# BSPD_v8.net
KiCad netlist of a schematic drawn in EAGLE
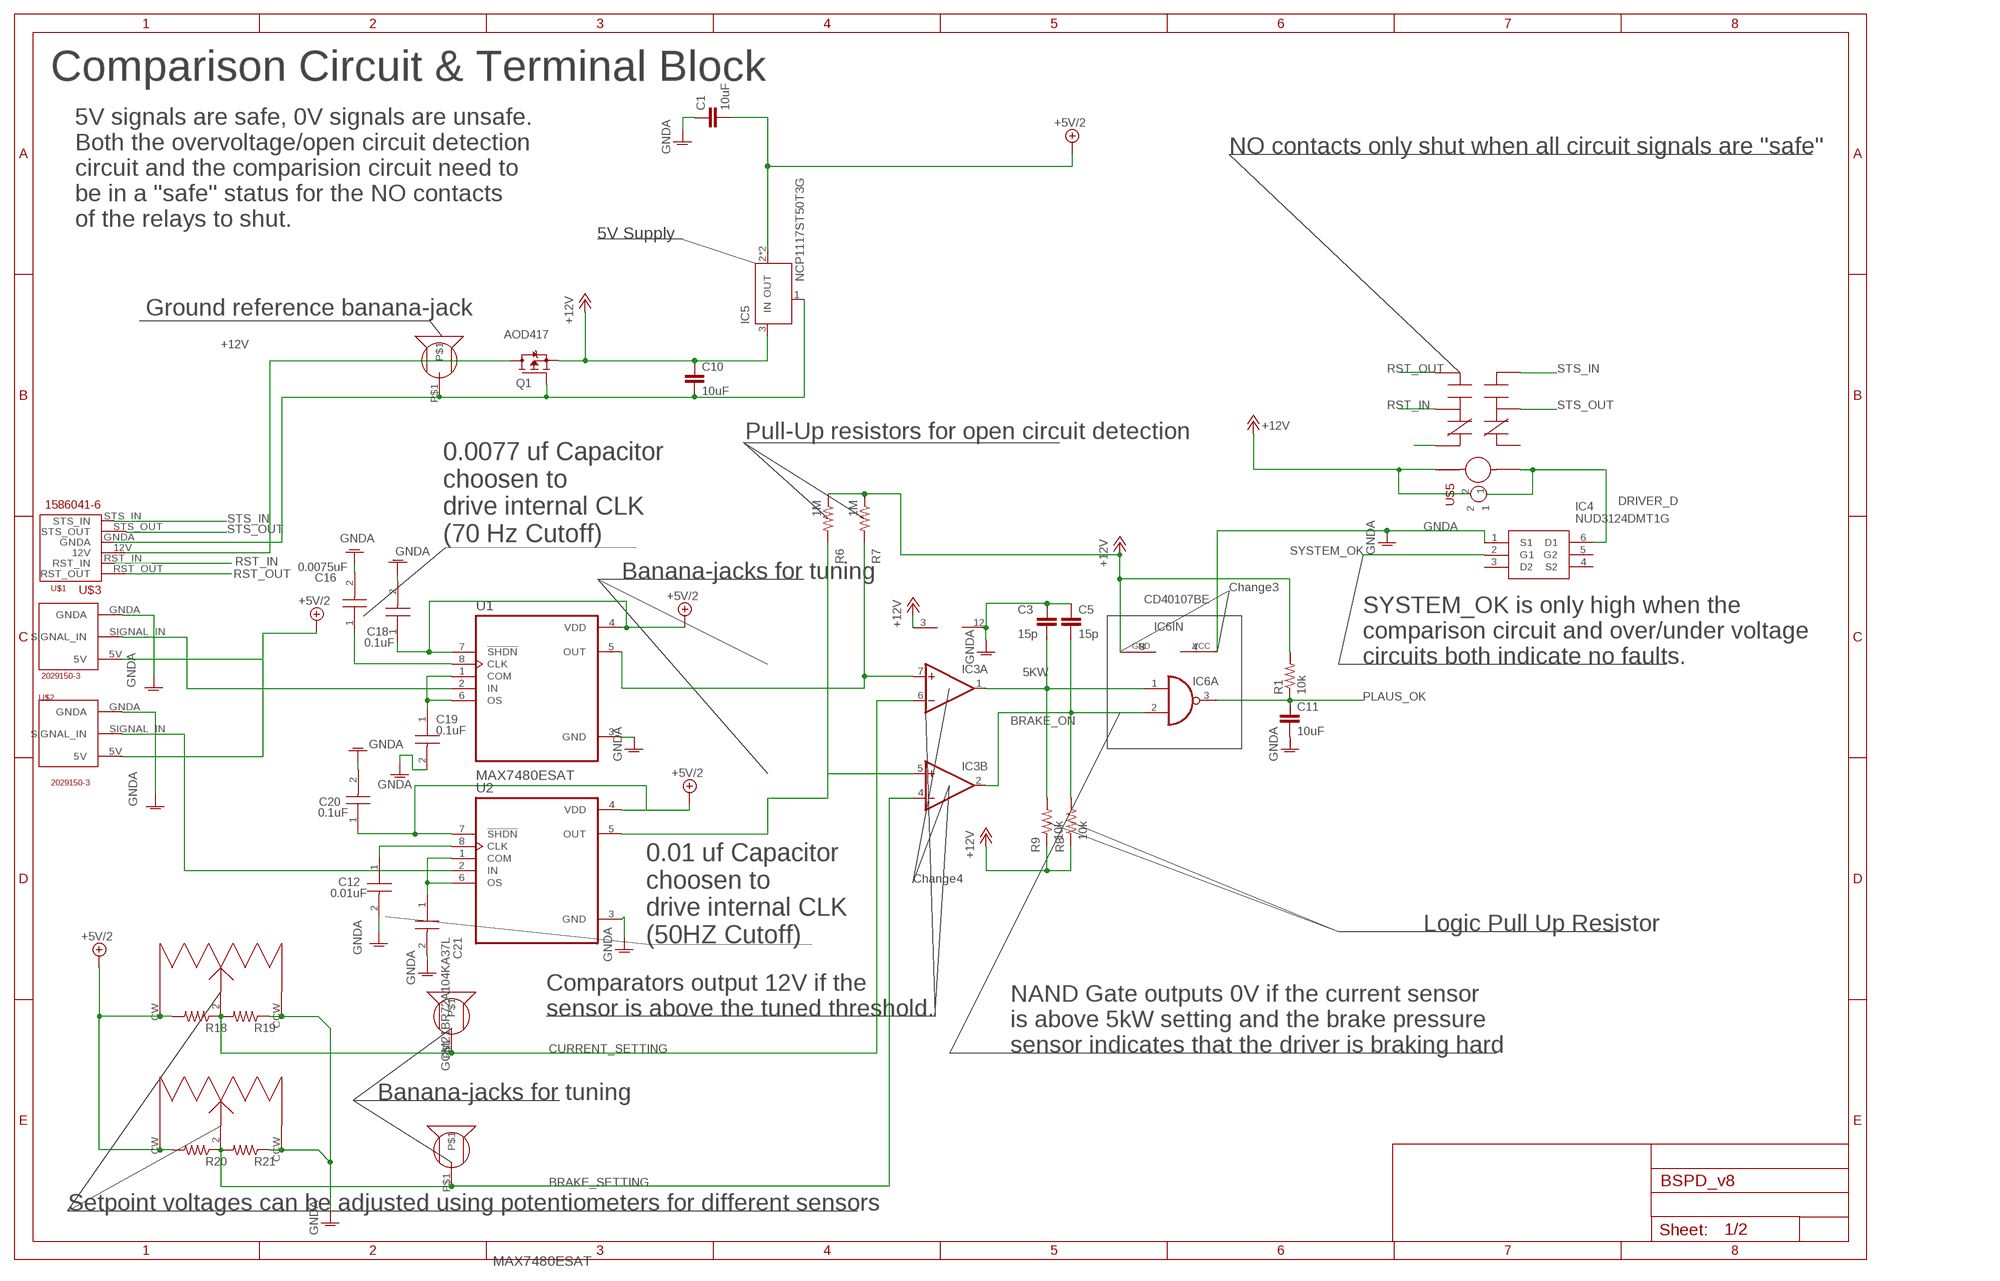
[diagram p0: schematic, sheet 1]
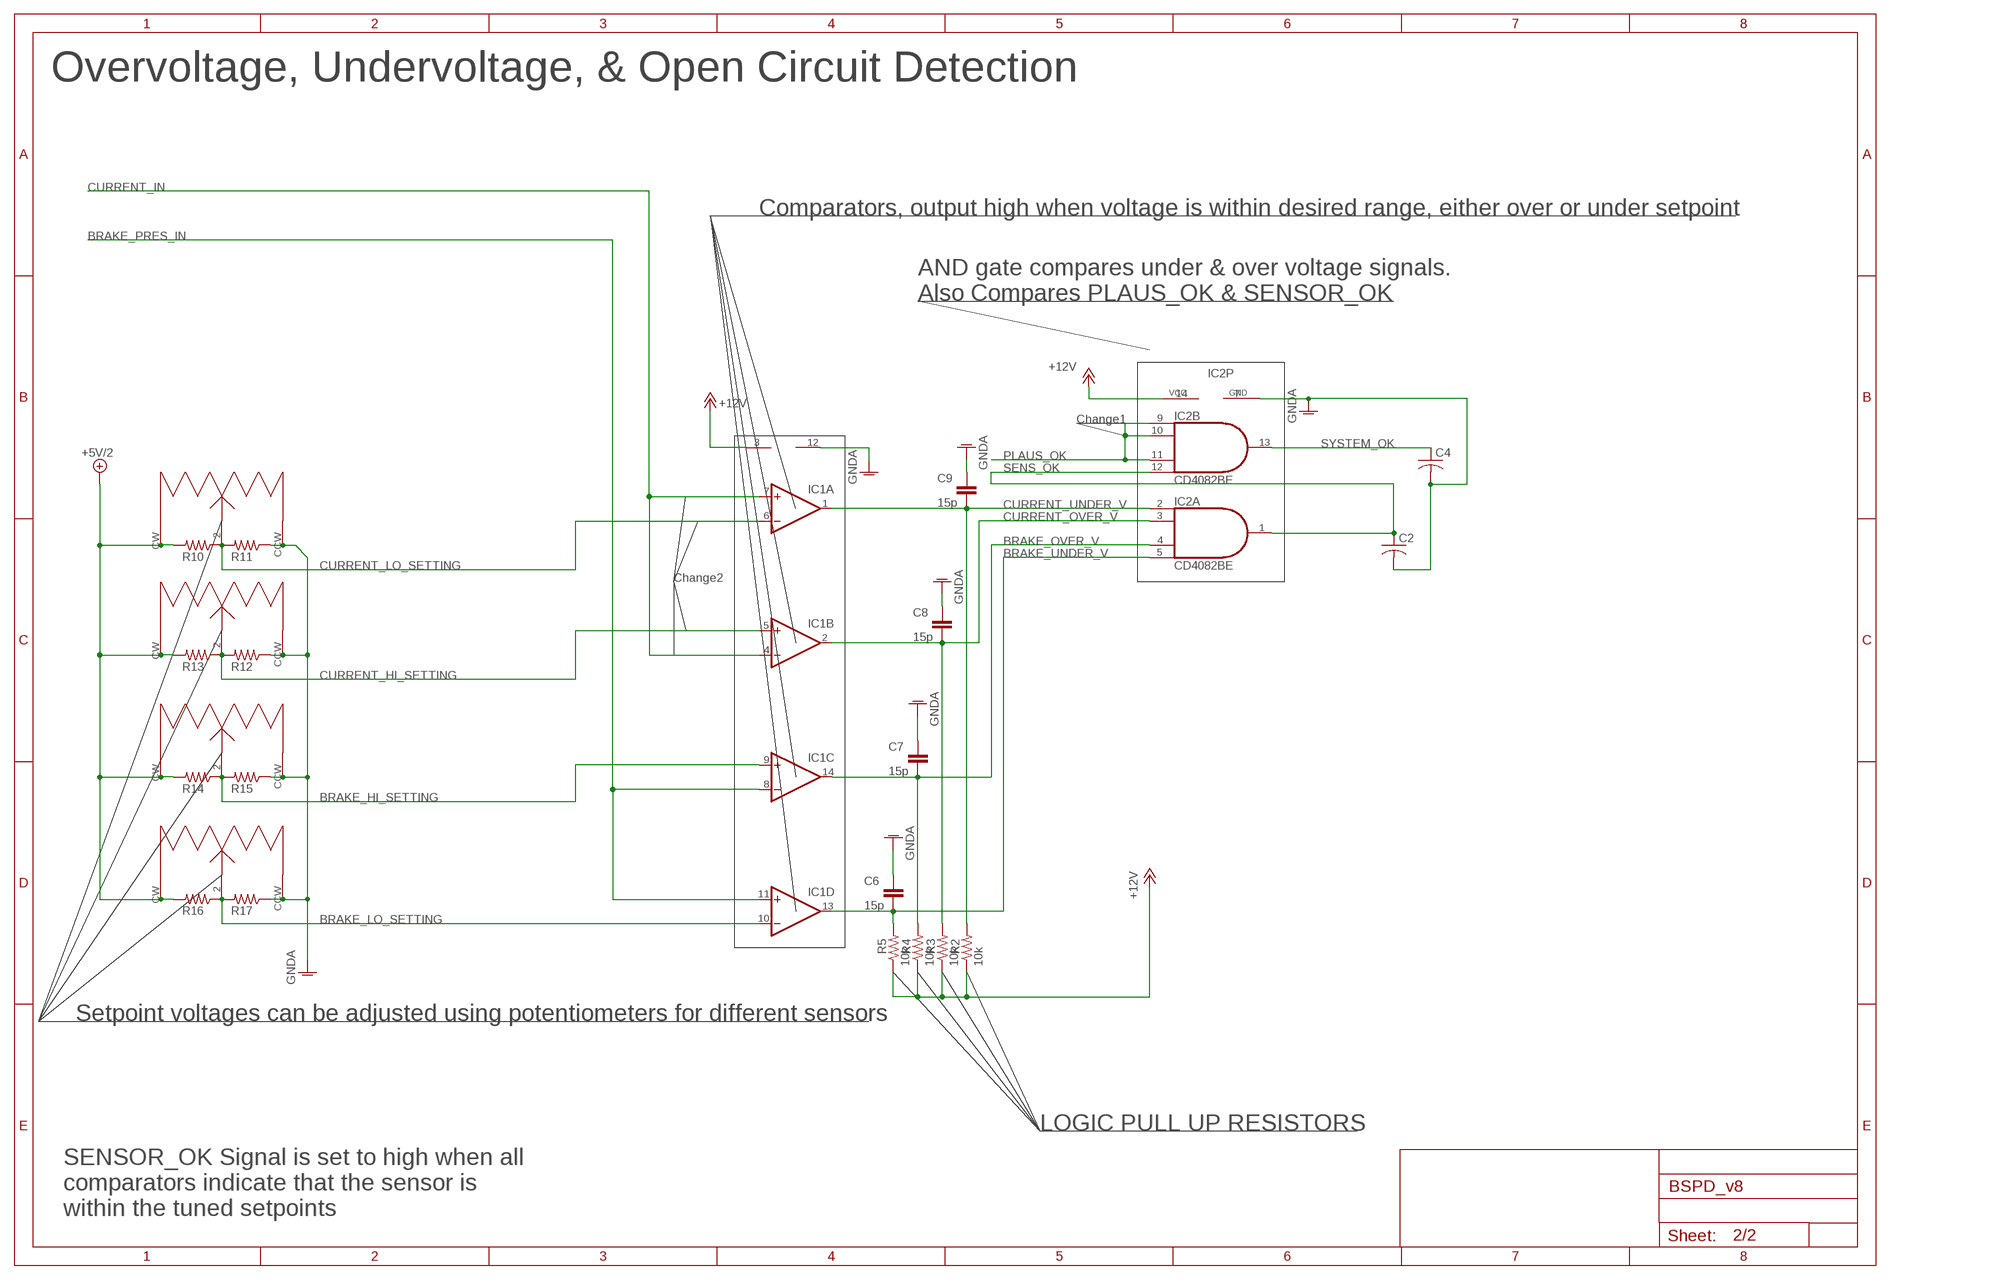
[diagram p1: schematic, sheet 2]

(export (version "E")
  (design (tool "Eeschema 10.0.6"))
  (components
    (comp (ref "C1")
      (value "10uF")
      (footprint "eagle-import:C0805")
      (libsource (lib "eagle-import") (part "resistor_348_C-EUC0805"))
    )
    (comp (ref "C3")
      (value "15p")
      (footprint "eagle-import:C0805")
      (libsource (lib "eagle-import") (part "C-EUC0805"))
    )
    (comp (ref "C5")
      (value "15p")
      (footprint "eagle-import:C0805")
      (libsource (lib "eagle-import") (part "C-EUC0805"))
    )
    (comp (ref "C10")
      (value "10uF")
      (footprint "eagle-import:C0805")
      (libsource (lib "eagle-import") (part "resistor_348_C-EUC0805"))
    )
    (comp (ref "C11")
      (value "10uF")
      (footprint "eagle-import:C0805")
      (libsource (lib "eagle-import") (part "resistor_348_C-EUC0805"))
    )
    (comp (ref "C12")
      (value "0.01uF")
      (footprint "eagle-import:CAPC2012X95N")
      (fields
        (field (name "MANUFACTURER_PART_NUMBER") "GRM2195C1H103JA01D")
        (field (name "MOUSER_PART_NUMBER") "81-GRM215C1H103JA01D")
      )
      (libsource (lib "eagle-import") (part "GRM2195C1H103JA01D"))
    )
    (comp (ref "C16")
      (value "0.0075uF")
      (footprint "eagle-import:CAPC2012X95N")
      (fields
        (field (name "MANUFACTURER_PART_NUMBER") "GRM2195C1H752JA01D")
        (field (name "MOUSER_PART_NUMBER") "81-GRM2195C1H752JA1D")
      )
      (libsource (lib "eagle-import") (part "GRM2195C1H752JA01D"))
    )
    (comp (ref "C18")
      (value "0.1uF")
      (footprint "eagle-import:CAPC2012X140N")
      (fields
        (field (name "MANUFACTURER_PART_NUMBER") "GCM21BR72A104KA37L")
        (field (name "MOUSER_PART_NUMBER") "81-GCM21BR72A104KA7L")
      )
      (libsource (lib "eagle-import") (part "GCM21BR72A104KA37L"))
    )
    (comp (ref "C19")
      (value "0.1uF")
      (footprint "eagle-import:CAPC2012X140N")
      (fields
        (field (name "MANUFACTURER_PART_NUMBER") "GCM21BR72A104KA37L")
        (field (name "MOUSER_PART_NUMBER") "81-GCM21BR72A104KA7L")
      )
      (libsource (lib "eagle-import") (part "GCM21BR72A104KA37L"))
    )
    (comp (ref "C20")
      (value "0.1uF")
      (footprint "eagle-import:CAPC2012X140N")
      (fields
        (field (name "MANUFACTURER_PART_NUMBER") "GCM21BR72A104KA37L")
        (field (name "MOUSER_PART_NUMBER") "81-GCM21BR72A104KA7L")
      )
      (libsource (lib "eagle-import") (part "GCM21BR72A104KA37L"))
    )
    (comp (ref "C21")
      (value "GCM21BR72A104KA37L")
      (footprint "eagle-import:CAPC2012X140N")
      (fields (field (name "MOUSER_PART_NUMBER") "81-GCM21BR72A104KA7L"))
      (libsource (lib "eagle-import") (part "GCM21BR72A104KA37L"))
    )
    (comp (ref "IC3")
      (value "4AMP_P11+7N")
      (footprint "eagle-import:DIL14")
      (libsource (lib "eagle-import") (part "4AMP_P11+7N"))
    )
    (comp (ref "IC4")
      (value "NUD3124DMT1G")
      (footprint "eagle-import:SOT95P275X110-6N")
      (fields (field (name "MOUSER_PART_NUMBER") "863-NUD3124DMT1G"))
      (libsource (lib "eagle-import") (part "NUD3124DMT1G"))
    )
    (comp (ref "IC5")
      (value "NCP1117ST50T3G")
      (footprint "eagle-import:SOT223")
      (libsource (lib "eagle-import") (part "NCP1117ST50T3G"))
    )
    (comp (ref "IC6")
      (value "CD40107BE")
      (footprint "eagle-import:DIL08")
      (libsource (lib "eagle-import") (part "CD40107BE"))
    )
    (comp (ref "Q1")
      (value "AOD417")
      (footprint "eagle-import:TO252")
      (fields (field (name "MF") "ON Semiconductor") (field (name "MP") "FDD4141"))
      (libsource (lib "eagle-import") (part "FDD4141TO252"))
    )
    (comp (ref "R1")
      (value "10k")
      (footprint "eagle-import:M0805")
      (libsource (lib "eagle-import") (part "R-US_M0805"))
    )
    (comp (ref "R6")
      (value "1M")
      (footprint "eagle-import:M0805")
      (libsource (lib "eagle-import") (part "resistor_R-US_M0805"))
    )
    (comp (ref "R7")
      (value "1M")
      (footprint "eagle-import:M0805")
      (libsource (lib "eagle-import") (part "resistor_R-US_M0805"))
    )
    (comp (ref "R8")
      (value "10k")
      (footprint "eagle-import:M0805")
      (libsource (lib "eagle-import") (part "resistor_R-US_M0805"))
    )
    (comp (ref "R9")
      (value "10k")
      (footprint "eagle-import:M0805")
      (libsource (lib "eagle-import") (part "resistor_R-US_M0805"))
    )
    (comp (ref "R18")
      (value "R-US_M0805")
      (footprint "eagle-import:M0805")
      (libsource (lib "eagle-import") (part "resistor_R-US_M0805"))
    )
    (comp (ref "R19")
      (value "R-US_M0805")
      (footprint "eagle-import:M0805")
      (libsource (lib "eagle-import") (part "resistor_R-US_M0805"))
    )
    (comp (ref "R20")
      (value "R-US_M0805")
      (footprint "eagle-import:M0805")
      (libsource (lib "eagle-import") (part "resistor_R-US_M0805"))
    )
    (comp (ref "R21")
      (value "R-US_M0805")
      (footprint "eagle-import:M0805")
      (libsource (lib "eagle-import") (part "resistor_R-US_M0805"))
    )
    (comp (ref "U$1")
      (value "2029150-3")
      (footprint "eagle-import:2029150-3")
      (libsource (lib "eagle-import") (part "2029150-3"))
    )
    (comp (ref "U$2")
      (value "2029150-3")
      (footprint "eagle-import:2029150-3")
      (libsource (lib "eagle-import") (part "2029150-3"))
    )
    (comp (ref "U$3")
      (value "1586041-6")
      (footprint "eagle-import:1586041-6")
      (libsource (lib "eagle-import") (part "1586041-6"))
    )
    (comp (ref "U$4")
      (value "BSPD_PARTS_MP_BANANA_PLUG")
      (footprint "eagle-import:BSPD_PARTS_BANANA_PLUG")
      (libsource (lib "eagle-import") (part "BSPD_PARTS_MP_BANANA_PLUG"))
    )
    (comp (ref "U$5")
      (value "SSL-LX3044ID-12V")
      (footprint "eagle-import:SSL-LX3044ID-12V")
      (libsource (lib "eagle-import") (part "SSL-LX3044ID-12V"))
    )
    (comp (ref "U$10")
      (value "POT_3310Y-025-103L")
      (footprint "eagle-import:3310Y")
      (libsource (lib "eagle-import") (part "POT_3310Y-025-103L"))
    )
    (comp (ref "U$11")
      (value "POT_3310Y-025-103L")
      (footprint "eagle-import:3310Y")
      (libsource (lib "eagle-import") (part "POT_3310Y-025-103L"))
    )
    (comp (ref "U$12")
      (value "BSPD_PARTS_RLY_V23079A1001B301")
      (footprint "eagle-import:BSPD_PARTS_V23079F1101B301")
      (libsource (lib "eagle-import") (part "BSPD_PARTS_RLY_V23079A1001B301"))
    )
    (comp (ref "U$18")
      (value "BSPD_PARTS_MP_BANANA_PLUG")
      (footprint "eagle-import:BSPD_PARTS_BANANA_PLUG")
      (libsource (lib "eagle-import") (part "BSPD_PARTS_MP_BANANA_PLUG"))
    )
    (comp (ref "U$19")
      (value "BSPD_PARTS_MP_BANANA_PLUG")
      (footprint "eagle-import:BSPD_PARTS_BANANA_PLUG")
      (libsource (lib "eagle-import") (part "BSPD_PARTS_MP_BANANA_PLUG"))
    )
    (comp (ref "U1")
      (value "MAX7480ESAT")
      (footprint "eagle-import:SOIC127P600X175-8N")
      (fields
        (field (name "DIGI-KEY_PART_NUMBER") "MAX7480ESA+-ND")
        (field (name "MF") "Maxim Integrated")
        (field (name "MP") "MAX7480ESA+")
      )
      (libsource (lib "eagle-import") (part "MAX7480ESAT"))
    )
    (comp (ref "U2")
      (value "MAX7480ESAT")
      (footprint "eagle-import:SOIC127P600X175-8N")
      (fields
        (field (name "DIGI-KEY_PART_NUMBER") "MAX7480ESA+-ND")
        (field (name "MF") "Maxim Integrated")
        (field (name "MP") "MAX7480ESA+")
      )
      (libsource (lib "eagle-import") (part "MAX7480ESAT"))
    )
    (comp (ref "C2")
      (value "C-USC0805")
      (footprint "eagle-import:C0805")
      (libsource (lib "eagle-import") (part "C-USC0805"))
    )
    (comp (ref "C4")
      (value "C-USC0805")
      (footprint "eagle-import:C0805")
      (libsource (lib "eagle-import") (part "C-USC0805"))
    )
    (comp (ref "C6")
      (value "15p")
      (footprint "eagle-import:C0805")
      (libsource (lib "eagle-import") (part "C-EUC0805"))
    )
    (comp (ref "C7")
      (value "15p")
      (footprint "eagle-import:C0805")
      (libsource (lib "eagle-import") (part "C-EUC0805"))
    )
    (comp (ref "C8")
      (value "15p")
      (footprint "eagle-import:C0805")
      (libsource (lib "eagle-import") (part "C-EUC0805"))
    )
    (comp (ref "C9")
      (value "15p")
      (footprint "eagle-import:C0805")
      (libsource (lib "eagle-import") (part "C-EUC0805"))
    )
    (comp (ref "IC1")
      (value "4AMP_P11+7N")
      (footprint "eagle-import:DIL14")
      (libsource (lib "eagle-import") (part "4AMP_P11+7N"))
    )
    (comp (ref "IC2")
      (value "CD4082BE")
      (footprint "eagle-import:DIL14")
      (libsource (lib "eagle-import") (part "7421NALS"))
    )
    (comp (ref "R2")
      (value "10k")
      (footprint "eagle-import:M0805")
      (libsource (lib "eagle-import") (part "resistor_R-US_M0805"))
    )
    (comp (ref "R3")
      (value "10k")
      (footprint "eagle-import:M0805")
      (libsource (lib "eagle-import") (part "resistor_R-US_M0805"))
    )
    (comp (ref "R4")
      (value "10k")
      (footprint "eagle-import:M0805")
      (libsource (lib "eagle-import") (part "resistor_R-US_M0805"))
    )
    (comp (ref "R5")
      (value "10k")
      (footprint "eagle-import:M0805")
      (libsource (lib "eagle-import") (part "resistor_R-US_M0805"))
    )
    (comp (ref "R10")
      (value "R-US_M0805")
      (footprint "eagle-import:M0805")
      (libsource (lib "eagle-import") (part "resistor_R-US_M0805"))
    )
    (comp (ref "R11")
      (value "R-US_M0805")
      (footprint "eagle-import:M0805")
      (libsource (lib "eagle-import") (part "resistor_R-US_M0805"))
    )
    (comp (ref "R12")
      (value "R-US_M0805")
      (footprint "eagle-import:M0805")
      (libsource (lib "eagle-import") (part "resistor_R-US_M0805"))
    )
    (comp (ref "R13")
      (value "R-US_M0805")
      (footprint "eagle-import:M0805")
      (libsource (lib "eagle-import") (part "resistor_R-US_M0805"))
    )
    (comp (ref "R14")
      (value "R-US_M0805")
      (footprint "eagle-import:M0805")
      (libsource (lib "eagle-import") (part "resistor_R-US_M0805"))
    )
    (comp (ref "R15")
      (value "R-US_M0805")
      (footprint "eagle-import:M0805")
      (libsource (lib "eagle-import") (part "resistor_R-US_M0805"))
    )
    (comp (ref "R16")
      (value "R-US_M0805")
      (footprint "eagle-import:M0805")
      (libsource (lib "eagle-import") (part "resistor_R-US_M0805"))
    )
    (comp (ref "R17")
      (value "R-US_M0805")
      (footprint "eagle-import:M0805")
      (libsource (lib "eagle-import") (part "resistor_R-US_M0805"))
    )
    (comp (ref "U$6")
      (value "POT_3310Y-025-103L")
      (footprint "eagle-import:3310Y")
      (libsource (lib "eagle-import") (part "POT_3310Y-025-103L"))
    )
    (comp (ref "U$7")
      (value "POT_3310Y-025-103L")
      (footprint "eagle-import:3310Y")
      (libsource (lib "eagle-import") (part "POT_3310Y-025-103L"))
    )
    (comp (ref "U$8")
      (value "POT_3310Y-025-103L")
      (footprint "eagle-import:3310Y")
      (libsource (lib "eagle-import") (part "POT_3310Y-025-103L"))
    )
    (comp (ref "U$9")
      (value "POT_3310Y-025-103L")
      (footprint "eagle-import:3310Y")
      (libsource (lib "eagle-import") (part "POT_3310Y-025-103L"))
    )
  )
  (nets
    (net (code "1") (name "+5V{slash}2") (class "Default")
      (node (ref "C1") (pin "2") (pinfunction "2_2") (pintype "passive"))
      (node (ref "C18") (pin "1") (pinfunction "1_1") (pintype "bidirectional"))
      (node (ref "C20") (pin "1") (pinfunction "1_1") (pintype "bidirectional"))
      (node (ref "IC5") (pin "2") (pinfunction "OUT_2") (pintype "passive"))
      (node (ref "IC5") (pin "4") (pinfunction "OUT_4") (pintype "passive"))
      (node (ref "R10") (pin "2") (pinfunction "2_2") (pintype "passive"))
      (node (ref "R13") (pin "2") (pinfunction "2_2") (pintype "passive"))
      (node (ref "R14") (pin "2") (pinfunction "2_2") (pintype "passive"))
      (node (ref "R16") (pin "2") (pinfunction "2_2") (pintype "passive"))
      (node (ref "R18") (pin "2") (pinfunction "2_2") (pintype "passive"))
      (node (ref "R20") (pin "2") (pinfunction "2_2") (pintype "passive"))
      (node (ref "U$1") (pin "5V") (pinfunction "5V_5V") (pintype "bidirectional"))
      (node (ref "U$10") (pin "CW") (pinfunction "CW_CW") (pintype "bidirectional"))
      (node (ref "U$11") (pin "CW") (pinfunction "CW_CW") (pintype "bidirectional"))
      (node (ref "U$2") (pin "5V") (pinfunction "5V_5V") (pintype "bidirectional"))
      (node (ref "U$6") (pin "CW") (pinfunction "CW_CW") (pintype "bidirectional"))
      (node (ref "U$7") (pin "CW") (pinfunction "CW_CW") (pintype "bidirectional"))
      (node (ref "U$8") (pin "CW") (pinfunction "CW_CW") (pintype "bidirectional"))
      (node (ref "U$9") (pin "CW") (pinfunction "CW_CW") (pintype "bidirectional"))
      (node (ref "U1") (pin "4") (pinfunction "VDD_4") (pintype "power_in"))
      (node (ref "U1") (pin "7") (pinfunction "~{SHDN}_7") (pintype "input"))
      (node (ref "U2") (pin "4") (pinfunction "VDD_4") (pintype "power_in"))
      (node (ref "U2") (pin "7") (pinfunction "~{SHDN}_7") (pintype "input"))
    )
    (net (code "2") (name "+12V") (class "Default")
      (node (ref "C10") (pin "1") (pinfunction "1_1") (pintype "passive"))
      (node (ref "IC1") (pin "3") (pinfunction "V+_3") (pintype "power_in"))
      (node (ref "IC2") (pin "14") (pinfunction "VCC_14") (pintype "power_in"))
      (node (ref "IC3") (pin "3") (pinfunction "V+_3") (pintype "power_in"))
      (node (ref "IC5") (pin "3") (pinfunction "IN_3") (pintype "input"))
      (node (ref "IC6") (pin "8") (pinfunction "GND_8") (pintype "power_in"))
      (node (ref "Q1") (pin "2") (pinfunction "S_2") (pintype "passive"))
      (node (ref "R1") (pin "2") (pinfunction "2_2") (pintype "passive"))
      (node (ref "R2") (pin "1") (pinfunction "1_1") (pintype "passive"))
      (node (ref "R3") (pin "1") (pinfunction "1_1") (pintype "passive"))
      (node (ref "R4") (pin "1") (pinfunction "1_1") (pintype "passive"))
      (node (ref "R5") (pin "1") (pinfunction "1_1") (pintype "passive"))
      (node (ref "R6") (pin "1") (pinfunction "1_1") (pintype "passive"))
      (node (ref "R7") (pin "1") (pinfunction "1_1") (pintype "passive"))
      (node (ref "R8") (pin "1") (pinfunction "1_1") (pintype "passive"))
      (node (ref "R9") (pin "1") (pinfunction "1_1") (pintype "passive"))
      (node (ref "U$12") (pin "1") (pinfunction "1_1") (pintype "bidirectional"))
      (node (ref "U$5") (pin "2") (pinfunction "2_2") (pintype "bidirectional"))
    )
    (net (code "3") (name "5KW") (class "Default")
      (node (ref "C3") (pin "2") (pinfunction "2_2") (pintype "passive"))
      (node (ref "IC3") (pin "1") (pinfunction "OUT_1") (pintype "output"))
      (node (ref "IC6") (pin "1") (pinfunction "I0_1") (pintype "input"))
      (node (ref "R9") (pin "2") (pinfunction "2_2") (pintype "passive"))
    )
    (net (code "4") (name "BRAKE_HI_SETTING") (class "Default")
      (node (ref "IC1") (pin "9") (pinfunction "+IN_9") (pintype "input"))
      (node (ref "R14") (pin "1") (pinfunction "1_1") (pintype "passive"))
      (node (ref "R15") (pin "2") (pinfunction "2_2") (pintype "passive"))
      (node (ref "U$8") (pin "2") (pinfunction "VO_2") (pintype "bidirectional"))
    )
    (net (code "5") (name "BRAKE_LO_SETTING") (class "Default")
      (node (ref "IC1") (pin "10") (pinfunction "-IN_10") (pintype "input"))
      (node (ref "R16") (pin "1") (pinfunction "1_1") (pintype "passive"))
      (node (ref "R17") (pin "2") (pinfunction "2_2") (pintype "passive"))
      (node (ref "U$9") (pin "2") (pinfunction "VO_2") (pintype "bidirectional"))
    )
    (net (code "6") (name "BRAKE_ON") (class "Default")
      (node (ref "C5") (pin "2") (pinfunction "2_2") (pintype "passive"))
      (node (ref "IC3") (pin "2") (pinfunction "OUT_2") (pintype "output"))
      (node (ref "IC6") (pin "2") (pinfunction "I1_2") (pintype "input"))
      (node (ref "R8") (pin "2") (pinfunction "2_2") (pintype "passive"))
    )
    (net (code "7") (name "BRAKE_OVER_V") (class "Default")
      (node (ref "C7") (pin "2") (pinfunction "2_2") (pintype "passive"))
      (node (ref "IC1") (pin "14") (pinfunction "OUT_14") (pintype "output"))
      (node (ref "IC2") (pin "4") (pinfunction "I2_4") (pintype "input"))
      (node (ref "R4") (pin "2") (pinfunction "2_2") (pintype "passive"))
    )
    (net (code "8") (name "BRAKE_PRES_IN") (class "Default")
      (node (ref "IC1") (pin "11") (pinfunction "+IN_11") (pintype "input"))
      (node (ref "IC1") (pin "8") (pinfunction "-IN_8") (pintype "input"))
      (node (ref "IC3") (pin "5") (pinfunction "+IN_5") (pintype "input"))
      (node (ref "R6") (pin "2") (pinfunction "2_2") (pintype "passive"))
      (node (ref "U2") (pin "5") (pinfunction "OUT_5") (pintype "output"))
    )
    (net (code "9") (name "BRAKE_SETTING") (class "Default")
      (node (ref "IC3") (pin "4") (pinfunction "-IN_4") (pintype "input"))
      (node (ref "R20") (pin "1") (pinfunction "1_1") (pintype "passive"))
      (node (ref "R21") (pin "2") (pinfunction "2_2") (pintype "passive"))
      (node (ref "U$10") (pin "2") (pinfunction "VO_2") (pintype "bidirectional"))
      (node (ref "U$19") (pin "P$1") (pinfunction "P$1_P$1") (pintype "bidirectional"))
    )
    (net (code "10") (name "BRAKE_UNDER_V") (class "Default")
      (node (ref "C6") (pin "2") (pinfunction "2_2") (pintype "passive"))
      (node (ref "IC1") (pin "13") (pinfunction "OUT_13") (pintype "output"))
      (node (ref "IC2") (pin "5") (pinfunction "I3_5") (pintype "input"))
      (node (ref "R5") (pin "2") (pinfunction "2_2") (pintype "passive"))
    )
    (net (code "11") (name "CURRENT_HI_SETTING") (class "Default")
      (node (ref "IC1") (pin "5") (pinfunction "+IN_5") (pintype "input"))
      (node (ref "R12") (pin "2") (pinfunction "2_2") (pintype "passive"))
      (node (ref "R13") (pin "1") (pinfunction "1_1") (pintype "passive"))
      (node (ref "U$7") (pin "2") (pinfunction "VO_2") (pintype "bidirectional"))
    )
    (net (code "12") (name "CURRENT_IN") (class "Default")
      (node (ref "IC1") (pin "4") (pinfunction "-IN_4") (pintype "input"))
      (node (ref "IC1") (pin "7") (pinfunction "+IN_7") (pintype "input"))
      (node (ref "IC3") (pin "7") (pinfunction "+IN_7") (pintype "input"))
      (node (ref "R7") (pin "2") (pinfunction "2_2") (pintype "passive"))
      (node (ref "U1") (pin "5") (pinfunction "OUT_5") (pintype "output"))
    )
    (net (code "13") (name "CURRENT_LO_SETTING") (class "Default")
      (node (ref "IC1") (pin "6") (pinfunction "-IN_6") (pintype "input"))
      (node (ref "R10") (pin "1") (pinfunction "1_1") (pintype "passive"))
      (node (ref "R11") (pin "2") (pinfunction "2_2") (pintype "passive"))
      (node (ref "U$6") (pin "2") (pinfunction "VO_2") (pintype "bidirectional"))
    )
    (net (code "14") (name "CURRENT_OVER_V") (class "Default")
      (node (ref "C8") (pin "2") (pinfunction "2_2") (pintype "passive"))
      (node (ref "IC1") (pin "2") (pinfunction "OUT_2") (pintype "output"))
      (node (ref "IC2") (pin "3") (pinfunction "I1_3") (pintype "input"))
      (node (ref "R3") (pin "2") (pinfunction "2_2") (pintype "passive"))
    )
    (net (code "15") (name "CURRENT_SETTING") (class "Default")
      (node (ref "IC3") (pin "6") (pinfunction "-IN_6") (pintype "input"))
      (node (ref "R18") (pin "1") (pinfunction "1_1") (pintype "passive"))
      (node (ref "R19") (pin "2") (pinfunction "2_2") (pintype "passive"))
      (node (ref "U$11") (pin "2") (pinfunction "VO_2") (pintype "bidirectional"))
      (node (ref "U$18") (pin "P$1") (pinfunction "P$1_P$1") (pintype "bidirectional"))
    )
    (net (code "16") (name "CURRENT_UNDER_V") (class "Default")
      (node (ref "C9") (pin "2") (pinfunction "2_2") (pintype "passive"))
      (node (ref "IC1") (pin "1") (pinfunction "OUT_1") (pintype "output"))
      (node (ref "IC2") (pin "2") (pinfunction "I0_2") (pintype "input"))
      (node (ref "R2") (pin "2") (pinfunction "2_2") (pintype "passive"))
    )
    (net (code "17") (name "DRIVER_D") (class "Default")
      (node (ref "IC4") (pin "6") (pinfunction "D1_6") (pintype "bidirectional"))
      (node (ref "U$12") (pin "12") (pinfunction "12_12") (pintype "bidirectional"))
      (node (ref "U$5") (pin "1") (pinfunction "1_1") (pintype "bidirectional"))
    )
    (net (code "18") (name "GNDA") (class "Default")
      (node (ref "C1") (pin "1") (pinfunction "1_1") (pintype "passive"))
      (node (ref "C10") (pin "2") (pinfunction "2_2") (pintype "passive"))
      (node (ref "C11") (pin "2") (pinfunction "2_2") (pintype "passive"))
      (node (ref "C12") (pin "2") (pinfunction "2_2") (pintype "bidirectional"))
      (node (ref "C16") (pin "2") (pinfunction "2_2") (pintype "bidirectional"))
      (node (ref "C18") (pin "2") (pinfunction "2_2") (pintype "bidirectional"))
      (node (ref "C19") (pin "2") (pinfunction "2_2") (pintype "bidirectional"))
      (node (ref "C2") (pin "2") (pinfunction "2_2") (pintype "passive"))
      (node (ref "C20") (pin "2") (pinfunction "2_2") (pintype "bidirectional"))
      (node (ref "C21") (pin "2") (pinfunction "2_2") (pintype "bidirectional"))
      (node (ref "C3") (pin "1") (pinfunction "1_1") (pintype "passive"))
      (node (ref "C4") (pin "2") (pinfunction "2_2") (pintype "passive"))
      (node (ref "C5") (pin "1") (pinfunction "1_1") (pintype "passive"))
      (node (ref "C6") (pin "1") (pinfunction "1_1") (pintype "passive"))
      (node (ref "C7") (pin "1") (pinfunction "1_1") (pintype "passive"))
      (node (ref "C8") (pin "1") (pinfunction "1_1") (pintype "passive"))
      (node (ref "C9") (pin "1") (pinfunction "1_1") (pintype "passive"))
      (node (ref "IC1") (pin "12") (pinfunction "V-_12") (pintype "power_in"))
      (node (ref "IC2") (pin "7") (pinfunction "GND_7") (pintype "power_in"))
      (node (ref "IC3") (pin "12") (pinfunction "V-_12") (pintype "power_in"))
      (node (ref "IC4") (pin "1") (pinfunction "S1_1") (pintype "bidirectional"))
      (node (ref "IC5") (pin "1") (pinfunction "GND_1") (pintype "power_in"))
      (node (ref "IC6") (pin "4") (pinfunction "VCC_4") (pintype "power_in"))
      (node (ref "Q1") (pin "1") (pinfunction "G_1") (pintype "passive"))
      (node (ref "R11") (pin "1") (pinfunction "1_1") (pintype "passive"))
      (node (ref "R12") (pin "1") (pinfunction "1_1") (pintype "passive"))
      (node (ref "R15") (pin "1") (pinfunction "1_1") (pintype "passive"))
      (node (ref "R17") (pin "1") (pinfunction "1_1") (pintype "passive"))
      (node (ref "R19") (pin "1") (pinfunction "1_1") (pintype "passive"))
      (node (ref "R21") (pin "1") (pinfunction "1_1") (pintype "passive"))
      (node (ref "U$1") (pin "GNDA") (pinfunction "GNDA_GNDA") (pintype "bidirectional"))
      (node (ref "U$10") (pin "CCW") (pinfunction "CCW_CCW") (pintype "bidirectional"))
      (node (ref "U$11") (pin "CCW") (pinfunction "CCW_CCW") (pintype "bidirectional"))
      (node (ref "U$2") (pin "GNDA") (pinfunction "GNDA_GNDA") (pintype "bidirectional"))
      (node (ref "U$3") (pin "GNDA") (pinfunction "GNDA_GNDA") (pintype "bidirectional"))
      (node (ref "U$4") (pin "P$1") (pinfunction "P$1_P$1") (pintype "bidirectional"))
      (node (ref "U$6") (pin "CCW") (pinfunction "CCW_CCW") (pintype "bidirectional"))
      (node (ref "U$7") (pin "CCW") (pinfunction "CCW_CCW") (pintype "bidirectional"))
      (node (ref "U$8") (pin "CCW") (pinfunction "CCW_CCW") (pintype "bidirectional"))
      (node (ref "U$9") (pin "CCW") (pinfunction "CCW_CCW") (pintype "bidirectional"))
      (node (ref "U1") (pin "3") (pinfunction "GND_3") (pintype "power_in"))
      (node (ref "U2") (pin "3") (pinfunction "GND_3") (pintype "power_in"))
    )
    (net (code "19") (name "Net-(Q1-D)") (class "Default")
      (node (ref "Q1") (pin "3") (pinfunction "D_3") (pintype "passive"))
      (node (ref "U$3") (pin "12V") (pinfunction "12V_12V") (pintype "bidirectional"))
    )
    (net (code "20") (name "Net-(U1-CLK)") (class "Default")
      (node (ref "C16") (pin "1") (pinfunction "1_1") (pintype "bidirectional"))
      (node (ref "U1") (pin "8") (pinfunction "CLK_8") (pintype "input"))
    )
    (net (code "21") (name "Net-(U1-COM)") (class "Default")
      (node (ref "C19") (pin "1") (pinfunction "1_1") (pintype "bidirectional"))
      (node (ref "U1") (pin "1") (pinfunction "COM_1") (pintype "input"))
      (node (ref "U1") (pin "6") (pinfunction "OS_6") (pintype "input"))
    )
    (net (code "22") (name "Net-(U1-IN)") (class "Default")
      (node (ref "U$1") (pin "SIGNAL_IN") (pinfunction "SIGNAL_IN_SIGNAL_IN") (pintype "bidirectional"))
      (node (ref "U1") (pin "2") (pinfunction "IN_2") (pintype "input"))
    )
    (net (code "23") (name "Net-(U2-CLK)") (class "Default")
      (node (ref "C12") (pin "1") (pinfunction "1_1") (pintype "bidirectional"))
      (node (ref "U2") (pin "8") (pinfunction "CLK_8") (pintype "input"))
    )
    (net (code "24") (name "Net-(U2-COM)") (class "Default")
      (node (ref "C21") (pin "1") (pinfunction "1_1") (pintype "bidirectional"))
      (node (ref "U2") (pin "1") (pinfunction "COM_1") (pintype "input"))
      (node (ref "U2") (pin "6") (pinfunction "OS_6") (pintype "input"))
    )
    (net (code "25") (name "Net-(U2-IN)") (class "Default")
      (node (ref "U$2") (pin "SIGNAL_IN") (pinfunction "SIGNAL_IN_SIGNAL_IN") (pintype "bidirectional"))
      (node (ref "U2") (pin "2") (pinfunction "IN_2") (pintype "input"))
    )
    (net (code "26") (name "PLAUS_OK") (class "Default")
      (node (ref "C11") (pin "1") (pinfunction "1_1") (pintype "passive"))
      (node (ref "IC2") (pin "10") (pinfunction "I1_10") (pintype "input"))
      (node (ref "IC2") (pin "11") (pinfunction "I2_11") (pintype "input"))
      (node (ref "IC2") (pin "9") (pinfunction "I0_9") (pintype "input"))
      (node (ref "IC6") (pin "3") (pinfunction "O_3") (pintype "output"))
      (node (ref "R1") (pin "1") (pinfunction "1_1") (pintype "passive"))
    )
    (net (code "27") (name "RST_IN") (class "Default")
      (node (ref "U$12") (pin "4") (pinfunction "4_4") (pintype "bidirectional"))
      (node (ref "U$3") (pin "RST_IN") (pinfunction "RST_IN_RST_IN") (pintype "bidirectional"))
    )
    (net (code "28") (name "RST_OUT") (class "Default")
      (node (ref "U$12") (pin "5") (pinfunction "5_5") (pintype "bidirectional"))
      (node (ref "U$3") (pin "RST_OUT") (pinfunction "RST_OUT_RST_OUT") (pintype "bidirectional"))
    )
    (net (code "29") (name "SENS_OK") (class "Default")
      (node (ref "C2") (pin "1") (pinfunction "1_1") (pintype "passive"))
      (node (ref "IC2") (pin "1") (pinfunction "O_1") (pintype "output"))
      (node (ref "IC2") (pin "12") (pinfunction "I3_12") (pintype "input"))
    )
    (net (code "30") (name "STS_IN") (class "Default")
      (node (ref "U$12") (pin "8") (pinfunction "8_8") (pintype "bidirectional"))
      (node (ref "U$3") (pin "STS_IN") (pinfunction "STS_IN_STS_IN") (pintype "bidirectional"))
    )
    (net (code "31") (name "STS_OUT") (class "Default")
      (node (ref "U$12") (pin "9") (pinfunction "9_9") (pintype "bidirectional"))
      (node (ref "U$3") (pin "STS_OUT") (pinfunction "STS_OUT_STS_OUT") (pintype "bidirectional"))
    )
    (net (code "32") (name "SYSTEM_OK") (class "Default")
      (node (ref "C4") (pin "1") (pinfunction "1_1") (pintype "passive"))
      (node (ref "IC2") (pin "13") (pinfunction "O_13") (pintype "output"))
      (node (ref "IC4") (pin "2") (pinfunction "G1_2") (pintype "bidirectional"))
    )
    (net (code "33") (name "unconnected-(IC4-D2-Pad3)") (class "Default")
      (node (ref "IC4") (pin "3") (pinfunction "D2_3") (pintype "bidirectional"))
    )
    (net (code "34") (name "unconnected-(IC4-G2-Pad5)") (class "Default")
      (node (ref "IC4") (pin "5") (pinfunction "G2_5") (pintype "bidirectional"))
    )
    (net (code "35") (name "unconnected-(IC4-S2-Pad4)") (class "Default")
      (node (ref "IC4") (pin "4") (pinfunction "S2_4") (pintype "bidirectional"))
    )
    (net (code "36") (name "unconnected-(U$12-Pad3)") (class "Default")
      (node (ref "U$12") (pin "3") (pinfunction "3_3") (pintype "bidirectional"))
    )
    (net (code "37") (name "unconnected-(U$12-Pad10)") (class "Default")
      (node (ref "U$12") (pin "10") (pinfunction "10_10") (pintype "bidirectional"))
    )
  )
)
